# connectorOut.net
KiCad netlist of a schematic drawn in Altium Designer
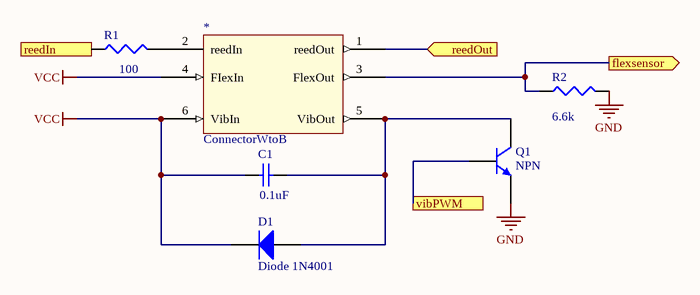
[diagram p0: connectorOut.SchDoc]

(export (version "E")
  (design (tool "Eeschema 10.0.6"))
  (components
    (comp (ref "*")
      (value "ConnectorWtoB")
      (footprint "Connector_wire_to_PCB")
      (libsource (lib "HGCDLibrary") (part "ConnectorWtoB"))
    )
    (comp (ref "C1")
      (value "0.1uF")
      (footprint "RAD-0.3")
      (description "Capacitor")
      (fields (field (name "Comment") "Cap") (field (name "PUBLISHER") "Altium Limited"))
      (libsource (lib "Miscellaneous Devices") (part "Cap"))
    )
    (comp (ref "D1")
      (value "Diode 1N4001")
      (footprint "DO-41")
      (description "1 Amp General Purpose Rectifier")
      (fields (field (name "PUBLISHER") "Altium Limited"))
      (libsource (lib "Miscellaneous Devices") (part "Diode 1N4001"))
    )
    (comp (ref "Q1")
      (value "NPN")
      (footprint "TO-226-AA")
      (description "NPN Bipolar Transistor")
      (fields (field (name "PUBLISHER") "Altium Limited"))
      (libsource (lib "Miscellaneous Devices") (part "NPN"))
    )
    (comp (ref "R1")
      (value "100")
      (footprint "J1-0603")
      (description "Resistor")
      (fields (field (name "PUBLISHER") "Altium Limited"))
      (libsource (lib "Miscellaneous Devices") (part "Res3"))
    )
    (comp (ref "R2")
      (value "6.6k")
      (footprint "J1-0603")
      (description "Resistor")
      (fields (field (name "Comment") "Res3") (field (name "PUBLISHER") "Altium Limited"))
      (libsource (lib "Miscellaneous Devices") (part "Res3"))
    )
  )
  (nets
    (net (code "1") (name "/flexsensor") (class "Default")
      (node (ref "*") (pin "3") (pinfunction "FlexOut_3") (pintype "output"))
      (node (ref "R2") (pin "1") (pinfunction "1_1") (pintype "passive"))
    )
    (net (code "2") (name "/reedIn") (class "Default")
      (node (ref "R1") (pin "1") (pinfunction "1_1") (pintype "passive"))
    )
    (net (code "3") (name "/reedOut") (class "Default")
      (node (ref "*") (pin "1") (pinfunction "reedOut_1") (pintype "output"))
    )
    (net (code "4") (name "/vibPWM") (class "Default")
      (node (ref "Q1") (pin "2") (pinfunction "B_2") (pintype "passive"))
    )
    (net (code "5") (name "GND") (class "Default")
      (node (ref "Q1") (pin "3") (pinfunction "E_3") (pintype "passive"))
      (node (ref "R2") (pin "2") (pinfunction "2_2") (pintype "passive"))
    )
    (net (code "6") (name "Net-(*-VibOut)") (class "Default")
      (node (ref "*") (pin "5") (pinfunction "VibOut_5") (pintype "output"))
      (node (ref "C1") (pin "2") (pinfunction "2_2") (pintype "passive"))
      (node (ref "D1") (pin "1") (pinfunction "A_1") (pintype "passive"))
      (node (ref "Q1") (pin "1") (pinfunction "C_1") (pintype "passive"))
    )
    (net (code "7") (name "Net-(*-reedIn)") (class "Default")
      (node (ref "*") (pin "2") (pinfunction "reedIn_2") (pintype "open_collector"))
      (node (ref "R1") (pin "2") (pinfunction "2_2") (pintype "passive"))
    )
    (net (code "8") (name "VCC") (class "Default")
      (node (ref "*") (pin "4") (pinfunction "FIexIn_4") (pintype "input"))
      (node (ref "*") (pin "6") (pinfunction "VibIn_6") (pintype "input"))
      (node (ref "C1") (pin "1") (pinfunction "1_1") (pintype "passive"))
      (node (ref "D1") (pin "2") (pinfunction "K_2") (pintype "passive"))
    )
  )
)
